# alim26.net
KiCad netlist of a schematic drawn in EAGLE
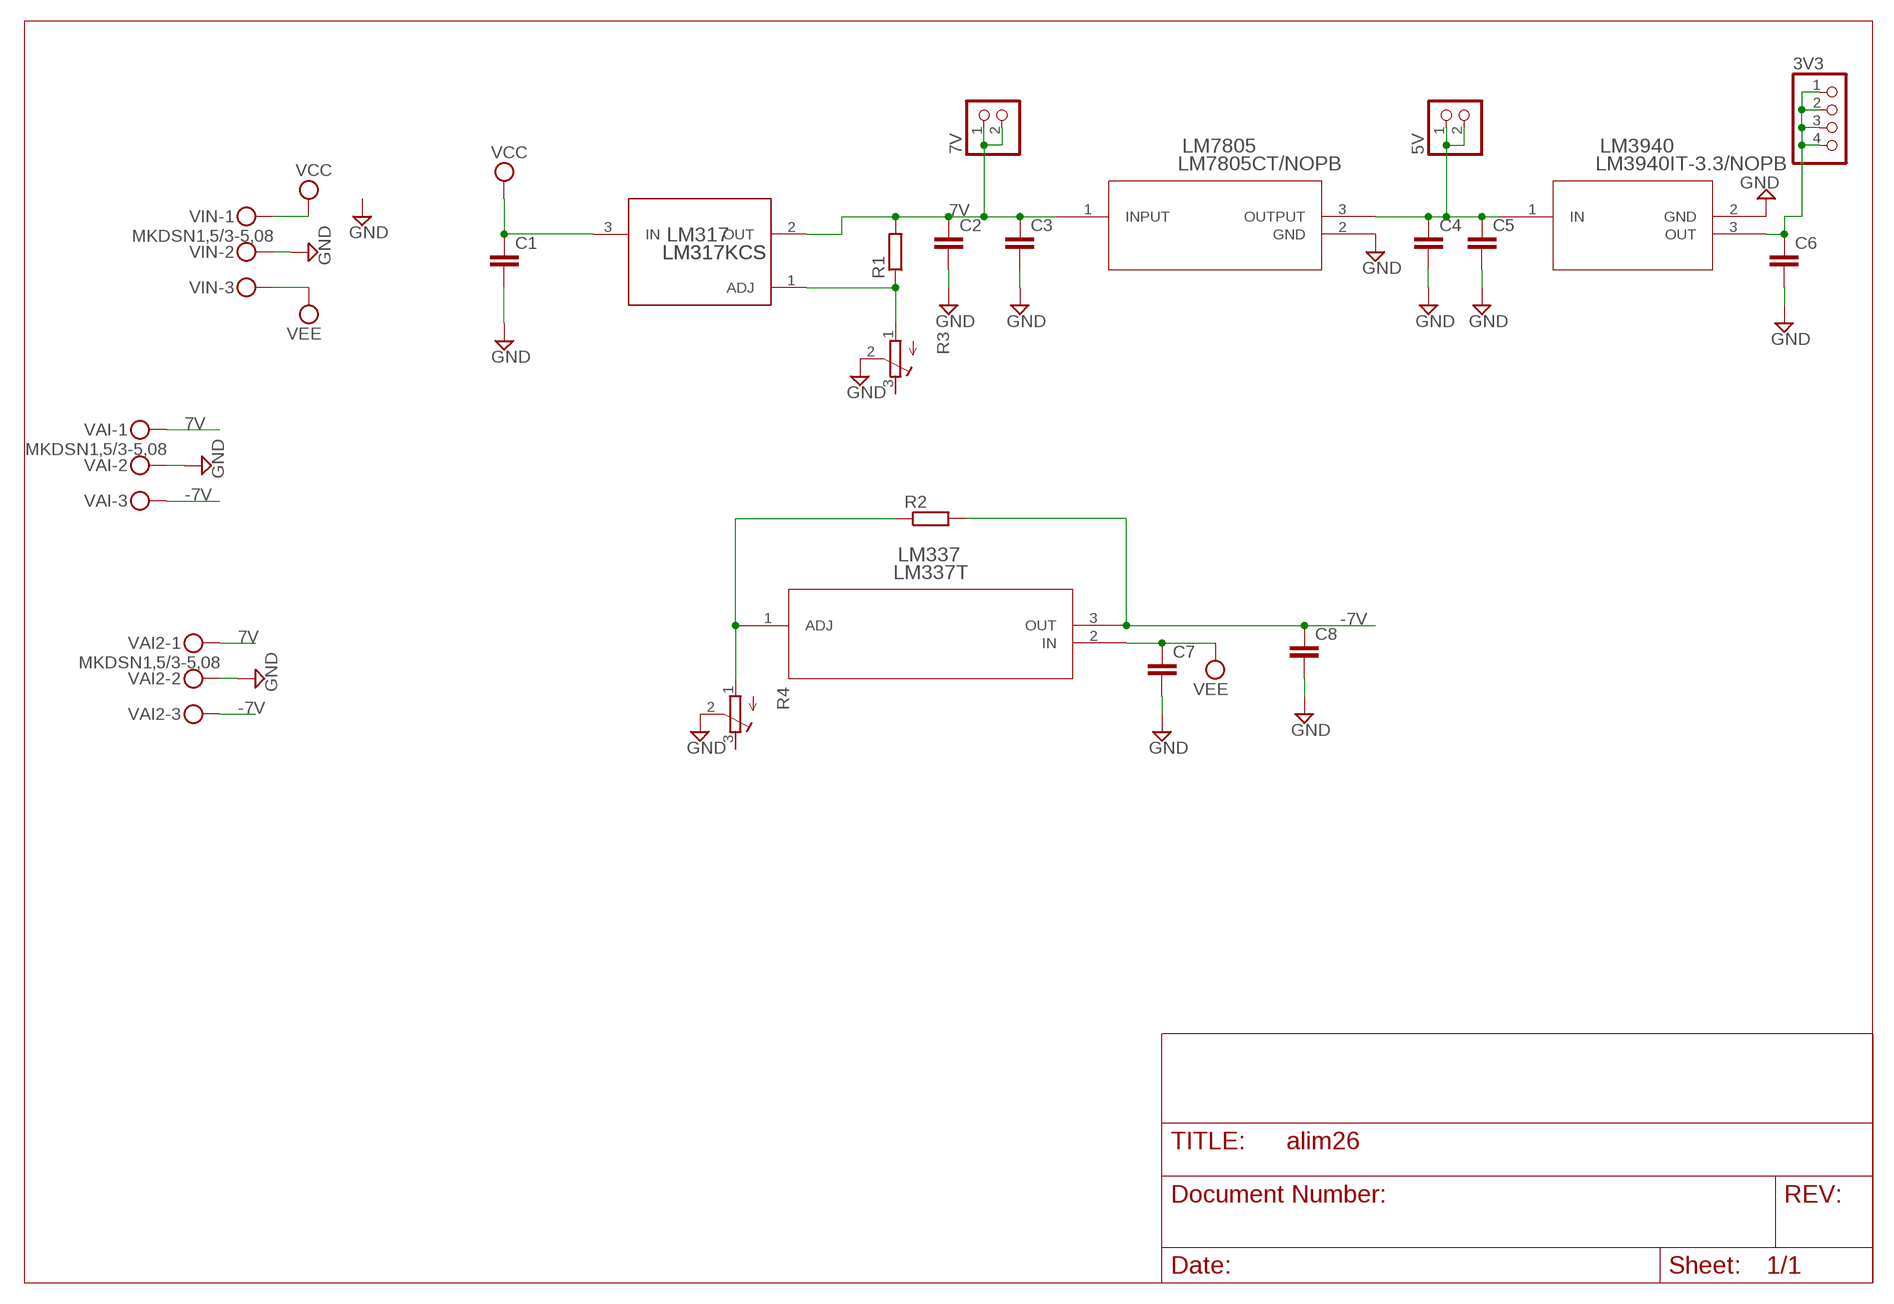
[diagram p0: schematic, sheet 1]

(export (version "E")
  (design (tool "Eeschema 10.0.6"))
  (components
    (comp (ref "3V3")
      (value "PINHD-1X4")
      (footprint "eagle-import:1X04")
      (libsource (lib "eagle-import") (part "PINHD-1X4"))
    )
    (comp (ref "5V")
      (value "PINHD-1X2")
      (footprint "eagle-import:1X02")
      (libsource (lib "eagle-import") (part "PINHD-1X2"))
    )
    (comp (ref "7V")
      (value "PINHD-1X2")
      (footprint "eagle-import:1X02")
      (libsource (lib "eagle-import") (part "PINHD-1X2"))
    )
    (comp (ref "C1")
      (value "C5/3")
      (footprint "eagle-import:C5B3")
      (libsource (lib "eagle-import") (part "C5/3"))
    )
    (comp (ref "C2")
      (value "C5/3")
      (footprint "eagle-import:C5B3")
      (libsource (lib "eagle-import") (part "C5/3"))
    )
    (comp (ref "C3")
      (value "C5/3")
      (footprint "eagle-import:C5B3")
      (libsource (lib "eagle-import") (part "C5/3"))
    )
    (comp (ref "C4")
      (value "C5/3")
      (footprint "eagle-import:C5B3")
      (libsource (lib "eagle-import") (part "C5/3"))
    )
    (comp (ref "C5")
      (value "C5/3")
      (footprint "eagle-import:C5B3")
      (libsource (lib "eagle-import") (part "C5/3"))
    )
    (comp (ref "C6")
      (value "C5/3")
      (footprint "eagle-import:C5B3")
      (libsource (lib "eagle-import") (part "C5/3"))
    )
    (comp (ref "C7")
      (value "C5/3")
      (footprint "eagle-import:C5B3")
      (libsource (lib "eagle-import") (part "C5/3"))
    )
    (comp (ref "C8")
      (value "C5/3")
      (footprint "eagle-import:C5B3")
      (libsource (lib "eagle-import") (part "C5/3"))
    )
    (comp (ref "LM317")
      (value "LM317KCS")
      (footprint "eagle-import:KCS0003A")
      (fields (field (name "COPYRIGHT") "Copyright (C) 2026 Ultra Librarian. All rights reserved."))
      (libsource (lib "eagle-import") (part "LM317KCS"))
    )
    (comp (ref "LM337")
      (value "LM337T")
      (footprint "eagle-import:T03B_TEX")
      (fields (field (name "COPYRIGHT") "Copyright (C) 2026 Ultra Librarian. All rights reserved."))
      (libsource (lib "eagle-import") (part "LM337T"))
    )
    (comp (ref "LM3940")
      (value "LM3940IT-3.3/NOPB")
      (footprint "eagle-import:T03B")
      (fields (field (name "COPYRIGHT") "Copyright (C) 2025 Ultra Librarian. All rights reserved."))
      (libsource (lib "eagle-import") (part "LM3940IT-3.3/NOPB"))
    )
    (comp (ref "LM7805")
      (value "LM7805CT/NOPB")
      (footprint "eagle-import:NDE3_TEX")
      (fields (field (name "COPYRIGHT") "Copyright (C) 2026 Ultra Librarian. All rights reserved."))
      (libsource (lib "eagle-import") (part "LM7805CT/NOPB"))
    )
    (comp (ref "R1")
      (value "R-EU_0207/10")
      (footprint "eagle-import:0207_10")
      (libsource (lib "eagle-import") (part "R-EU_0207/10"))
    )
    (comp (ref "R2")
      (value "R-EU_0207/10")
      (footprint "eagle-import:0207_10")
      (libsource (lib "eagle-import") (part "R-EU_0207/10"))
    )
    (comp (ref "R3")
      (value "R-TRIMM64Y")
      (footprint "eagle-import:RTRIM64Y")
      (libsource (lib "eagle-import") (part "R-TRIMM64Y"))
    )
    (comp (ref "R4")
      (value "R-TRIMM64Y")
      (footprint "eagle-import:RTRIM64Y")
      (libsource (lib "eagle-import") (part "R-TRIMM64Y"))
    )
    (comp (ref "VAI")
      (value "MKDSN1,5/3-5,08")
      (footprint "eagle-import:MKDSN1,5_3-5,08")
      (libsource (lib "eagle-import") (part "MKDSN1,5/3-5,08"))
    )
    (comp (ref "VAI2")
      (value "MKDSN1,5/3-5,08")
      (footprint "eagle-import:MKDSN1,5_3-5,08")
      (libsource (lib "eagle-import") (part "MKDSN1,5/3-5,08"))
    )
    (comp (ref "VIN")
      (value "MKDSN1,5/3-5,08")
      (footprint "eagle-import:MKDSN1,5_3-5,08")
      (libsource (lib "eagle-import") (part "MKDSN1,5/3-5,08"))
    )
  )
  (nets
    (net (code "1") (name "/-7V") (class "Default")
      (node (ref "C8") (pin "1") (pinfunction "1_1") (pintype "passive"))
      (node (ref "LM337") (pin "3") (pinfunction "OUT_3") (pintype "power_in"))
      (node (ref "R2") (pin "2") (pinfunction "2_2") (pintype "passive"))
      (node (ref "VAI") (pin "3") (pinfunction "KL_3") (pintype "passive"))
      (node (ref "VAI2") (pin "3") (pinfunction "KL_3") (pintype "passive"))
    )
    (net (code "2") (name "/7V") (class "Default")
      (node (ref "7V") (pin "1") (pinfunction "1_1") (pintype "passive"))
      (node (ref "7V") (pin "2") (pinfunction "2_2") (pintype "passive"))
      (node (ref "C2") (pin "1") (pinfunction "1_1") (pintype "passive"))
      (node (ref "C3") (pin "1") (pinfunction "1_1") (pintype "passive"))
      (node (ref "LM317") (pin "2") (pinfunction "OUT_2") (pintype "power_in"))
      (node (ref "LM7805") (pin "1") (pinfunction "INPUT_1") (pintype "input"))
      (node (ref "R1") (pin "2") (pinfunction "2_2") (pintype "passive"))
      (node (ref "VAI") (pin "1") (pinfunction "KL_1") (pintype "passive"))
      (node (ref "VAI2") (pin "1") (pinfunction "KL_1") (pintype "passive"))
    )
    (net (code "3") (name "GND") (class "Default")
      (node (ref "C1") (pin "2") (pinfunction "2_2") (pintype "passive"))
      (node (ref "C2") (pin "2") (pinfunction "2_2") (pintype "passive"))
      (node (ref "C3") (pin "2") (pinfunction "2_2") (pintype "passive"))
      (node (ref "C4") (pin "2") (pinfunction "2_2") (pintype "passive"))
      (node (ref "C5") (pin "2") (pinfunction "2_2") (pintype "passive"))
      (node (ref "C6") (pin "2") (pinfunction "2_2") (pintype "passive"))
      (node (ref "C7") (pin "2") (pinfunction "2_2") (pintype "passive"))
      (node (ref "C8") (pin "2") (pinfunction "2_2") (pintype "passive"))
      (node (ref "LM3940") (pin "2") (pinfunction "GND_2") (pintype "passive"))
      (node (ref "LM7805") (pin "2") (pinfunction "GND_2") (pintype "power_in"))
      (node (ref "R3") (pin "2") (pinfunction "S_2") (pintype "passive"))
      (node (ref "R4") (pin "2") (pinfunction "S_2") (pintype "passive"))
      (node (ref "VAI") (pin "2") (pinfunction "KL_2") (pintype "passive"))
      (node (ref "VAI2") (pin "2") (pinfunction "KL_2") (pintype "passive"))
      (node (ref "VIN") (pin "2") (pinfunction "KL_2") (pintype "passive"))
    )
    (net (code "4") (name "Net-(LM317-ADJ)") (class "Default")
      (node (ref "LM317") (pin "1") (pinfunction "ADJ_1") (pintype "input"))
      (node (ref "R1") (pin "1") (pinfunction "1_1") (pintype "passive"))
      (node (ref "R3") (pin "1") (pinfunction "A_1") (pintype "passive"))
    )
    (net (code "5") (name "Net-(LM337-ADJ)") (class "Default")
      (node (ref "LM337") (pin "1") (pinfunction "ADJ_1") (pintype "input"))
      (node (ref "R2") (pin "1") (pinfunction "1_1") (pintype "passive"))
      (node (ref "R4") (pin "1") (pinfunction "A_1") (pintype "passive"))
    )
    (net (code "6") (name "Net-(LM3940-IN)") (class "Default")
      (node (ref "5V") (pin "1") (pinfunction "1_1") (pintype "passive"))
      (node (ref "5V") (pin "2") (pinfunction "2_2") (pintype "passive"))
      (node (ref "C4") (pin "1") (pinfunction "1_1") (pintype "passive"))
      (node (ref "C5") (pin "1") (pinfunction "1_1") (pintype "passive"))
      (node (ref "LM3940") (pin "1") (pinfunction "IN_1") (pintype "input"))
      (node (ref "LM7805") (pin "3") (pinfunction "OUTPUT_3") (pintype "output"))
    )
    (net (code "7") (name "Net-(LM3940-OUT)") (class "Default")
      (node (ref "3V3") (pin "1") (pinfunction "1_1") (pintype "passive"))
      (node (ref "3V3") (pin "2") (pinfunction "2_2") (pintype "passive"))
      (node (ref "3V3") (pin "3") (pinfunction "3_3") (pintype "passive"))
      (node (ref "3V3") (pin "4") (pinfunction "4_4") (pintype "passive"))
      (node (ref "C6") (pin "1") (pinfunction "1_1") (pintype "passive"))
      (node (ref "LM3940") (pin "3") (pinfunction "OUT_3") (pintype "output"))
    )
    (net (code "8") (name "VCC") (class "Default")
      (node (ref "C1") (pin "1") (pinfunction "1_1") (pintype "passive"))
      (node (ref "LM317") (pin "3") (pinfunction "IN_3") (pintype "power_in"))
      (node (ref "VIN") (pin "1") (pinfunction "KL_1") (pintype "passive"))
    )
    (net (code "9") (name "VEE") (class "Default")
      (node (ref "C7") (pin "1") (pinfunction "1_1") (pintype "passive"))
      (node (ref "LM337") (pin "2") (pinfunction "IN_2") (pintype "power_in"))
      (node (ref "VIN") (pin "3") (pinfunction "KL_3") (pintype "passive"))
    )
    (net (code "10") (name "unconnected-(R3-E-Pad3)") (class "Default")
      (node (ref "R3") (pin "3") (pinfunction "E_3") (pintype "passive"))
    )
    (net (code "11") (name "unconnected-(R4-E-Pad3)") (class "Default")
      (node (ref "R4") (pin "3") (pinfunction "E_3") (pintype "passive"))
    )
  )
)
